# Buffer_Sheet1.net
KiCad netlist of a schematic drawn in Altium Designer
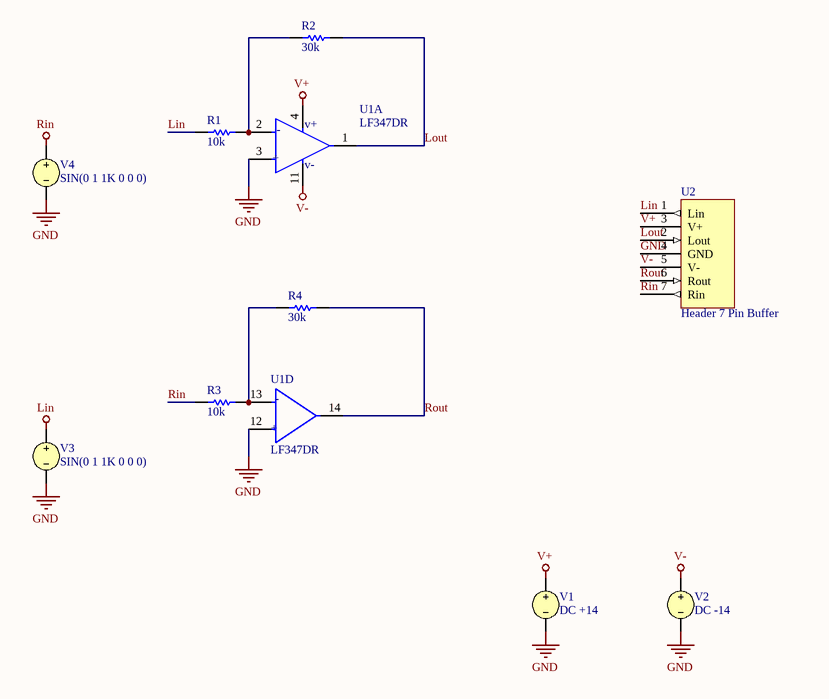
[diagram p0: Buffer_Sheet1.SchDoc]

(export (version "E")
  (design (tool "Eeschema 10.0.6"))
  (components
    (comp (ref "R1")
      (value "10k")
      (footprint "KBS_SMD0603")
      (description "Fixed Resistor, 0.25W, 10000ohm, 200V, Surface Mount, 1206")
      (fields (field (name "TOLERANCE") "1%") (field (name "POWER") "250mW"))
      (libsource (lib "ECEN299_Library") (part "CMP-009-00177-1"))
    )
    (comp (ref "R2")
      (value "30k")
      (footprint "KBS_SMD0603")
      (description "Fixed Resistor, 0.25W, 10000ohm, 200V, Surface Mount, 1206")
      (fields (field (name "TOLERANCE") "1%") (field (name "POWER") "250mW"))
      (libsource (lib "ECEN299_Library") (part "CMP-009-00177-1"))
    )
    (comp (ref "R3")
      (value "10k")
      (footprint "KBS_SMD0603")
      (description "Fixed Resistor, 0.25W, 10000ohm, 200V, Surface Mount, 1206")
      (fields (field (name "TOLERANCE") "1%") (field (name "POWER") "250mW"))
      (libsource (lib "ECEN299_Library") (part "CMP-009-00177-1"))
    )
    (comp (ref "R4")
      (value "30k")
      (footprint "KBS_SMD0603")
      (description "Fixed Resistor, 0.25W, 10000ohm, 200V, Surface Mount, 1206")
      (fields (field (name "TOLERANCE") "1%") (field (name "POWER") "250mW"))
      (libsource (lib "ECEN299_Library") (part "CMP-009-00177-1"))
    )
    (comp (ref "U1")
      (value "LF347DR")
      (footprint "KBS_SO14_w_Guide_Pin_Holes")
      (description "Operational Amplifier, 4 Func, 13000uV Offset-Max, JFET, PDSO14")
      (fields (field (name "MANUFACTURER") "Texas Instruments"))
      (libsource (lib "ECEN299_Library") (part "CMP-014-00002-1"))
    )
    (comp (ref "U2")
      (value "Header 7 Pin Buffer")
      (footprint "KBS_7pin_Header_Buffer")
      (description "7 Pin Header for ECEN 299 buffer PCB.")
      (libsource (lib "ECEN299_Library") (part "CMP-002-00071-2"))
    )
    (comp (ref "V1")
      (value "DC +14")
      (description "Voltage Source")
      (fields (field (name "PUBLISHER") "Altium Limited"))
      (libsource (lib "Simulation Generic Components") (part "VSRC"))
    )
    (comp (ref "V2")
      (value "DC -14")
      (description "Voltage Source")
      (fields (field (name "PUBLISHER") "Altium Limited"))
      (libsource (lib "Simulation Generic Components") (part "VSRC"))
    )
    (comp (ref "V3")
      (value "SIN(0 1 1K 0 0 0)")
      (description "Voltage Source")
      (fields (field (name "PUBLISHER") "Altium Limited"))
      (libsource (lib "Simulation Generic Components") (part "VSRC"))
    )
    (comp (ref "V4")
      (value "SIN(0 1 1K 0 0 0)")
      (description "Voltage Source")
      (fields (field (name "PUBLISHER") "Altium Limited"))
      (libsource (lib "Simulation Generic Components") (part "VSRC"))
    )
  )
  (nets
    (net (code "1") (name "/Lout") (class "Default")
      (node (ref "R2") (pin "2") (pinfunction "2_2") (pintype "passive"))
      (node (ref "U1") (pin "1") (pinfunction "1OUT_1") (pintype "passive"))
      (node (ref "U2") (pin "2") (pinfunction "Lout_2") (pintype "input"))
    )
    (net (code "2") (name "/Rout") (class "Default")
      (node (ref "R4") (pin "2") (pinfunction "2_2") (pintype "passive"))
      (node (ref "U1") (pin "14") (pinfunction "4OUT_14") (pintype "passive"))
      (node (ref "U2") (pin "6") (pinfunction "Rout_6") (pintype "input"))
    )
    (net (code "3") (name "GND") (class "Default")
      (node (ref "U1") (pin "12") (pinfunction "4IN+_12") (pintype "tri_state"))
      (node (ref "U1") (pin "3") (pinfunction "1IN+_3") (pintype "tri_state"))
      (node (ref "U2") (pin "4") (pinfunction "GND_4") (pintype "power_in"))
      (node (ref "V1") (pin "2") (pinfunction "2_2") (pintype "passive"))
      (node (ref "V2") (pin "2") (pinfunction "2_2") (pintype "passive"))
      (node (ref "V3") (pin "2") (pinfunction "2_2") (pintype "passive"))
      (node (ref "V4") (pin "2") (pinfunction "2_2") (pintype "passive"))
    )
    (net (code "4") (name "Lin") (class "Default")
      (node (ref "R1") (pin "1") (pinfunction "1_1") (pintype "passive"))
      (node (ref "U2") (pin "1") (pinfunction "Lin_1") (pintype "output"))
      (node (ref "V3") (pin "1") (pinfunction "1_1") (pintype "passive"))
    )
    (net (code "5") (name "Net-(U1A-1IN-)") (class "Default")
      (node (ref "R1") (pin "2") (pinfunction "2_2") (pintype "passive"))
      (node (ref "R2") (pin "1") (pinfunction "1_1") (pintype "passive"))
      (node (ref "U1") (pin "2") (pinfunction "1IN-_2") (pintype "tri_state"))
    )
    (net (code "6") (name "Net-(U1D-4IN-)") (class "Default")
      (node (ref "R3") (pin "2") (pinfunction "2_2") (pintype "passive"))
      (node (ref "R4") (pin "1") (pinfunction "1_1") (pintype "passive"))
      (node (ref "U1") (pin "13") (pinfunction "4IN-_13") (pintype "tri_state"))
    )
    (net (code "7") (name "Rin") (class "Default")
      (node (ref "R3") (pin "1") (pinfunction "1_1") (pintype "passive"))
      (node (ref "U2") (pin "7") (pinfunction "Rin_7") (pintype "output"))
      (node (ref "V4") (pin "1") (pinfunction "1_1") (pintype "passive"))
    )
    (net (code "8") (name "V+") (class "Default")
      (node (ref "U1") (pin "4") (pinfunction "VCC+_4") (pintype "power_in"))
      (node (ref "U2") (pin "3") (pinfunction "V+_3") (pintype "power_in"))
      (node (ref "V1") (pin "1") (pinfunction "1_1") (pintype "passive"))
    )
    (net (code "9") (name "V-") (class "Default")
      (node (ref "U1") (pin "11") (pinfunction "VCC-_11") (pintype "power_in"))
      (node (ref "U2") (pin "5") (pinfunction "V-_5") (pintype "power_in"))
      (node (ref "V2") (pin "1") (pinfunction "1_1") (pintype "passive"))
    )
  )
)
